# DX_HRII2.net
KiCad netlist of a schematic drawn in EAGLE
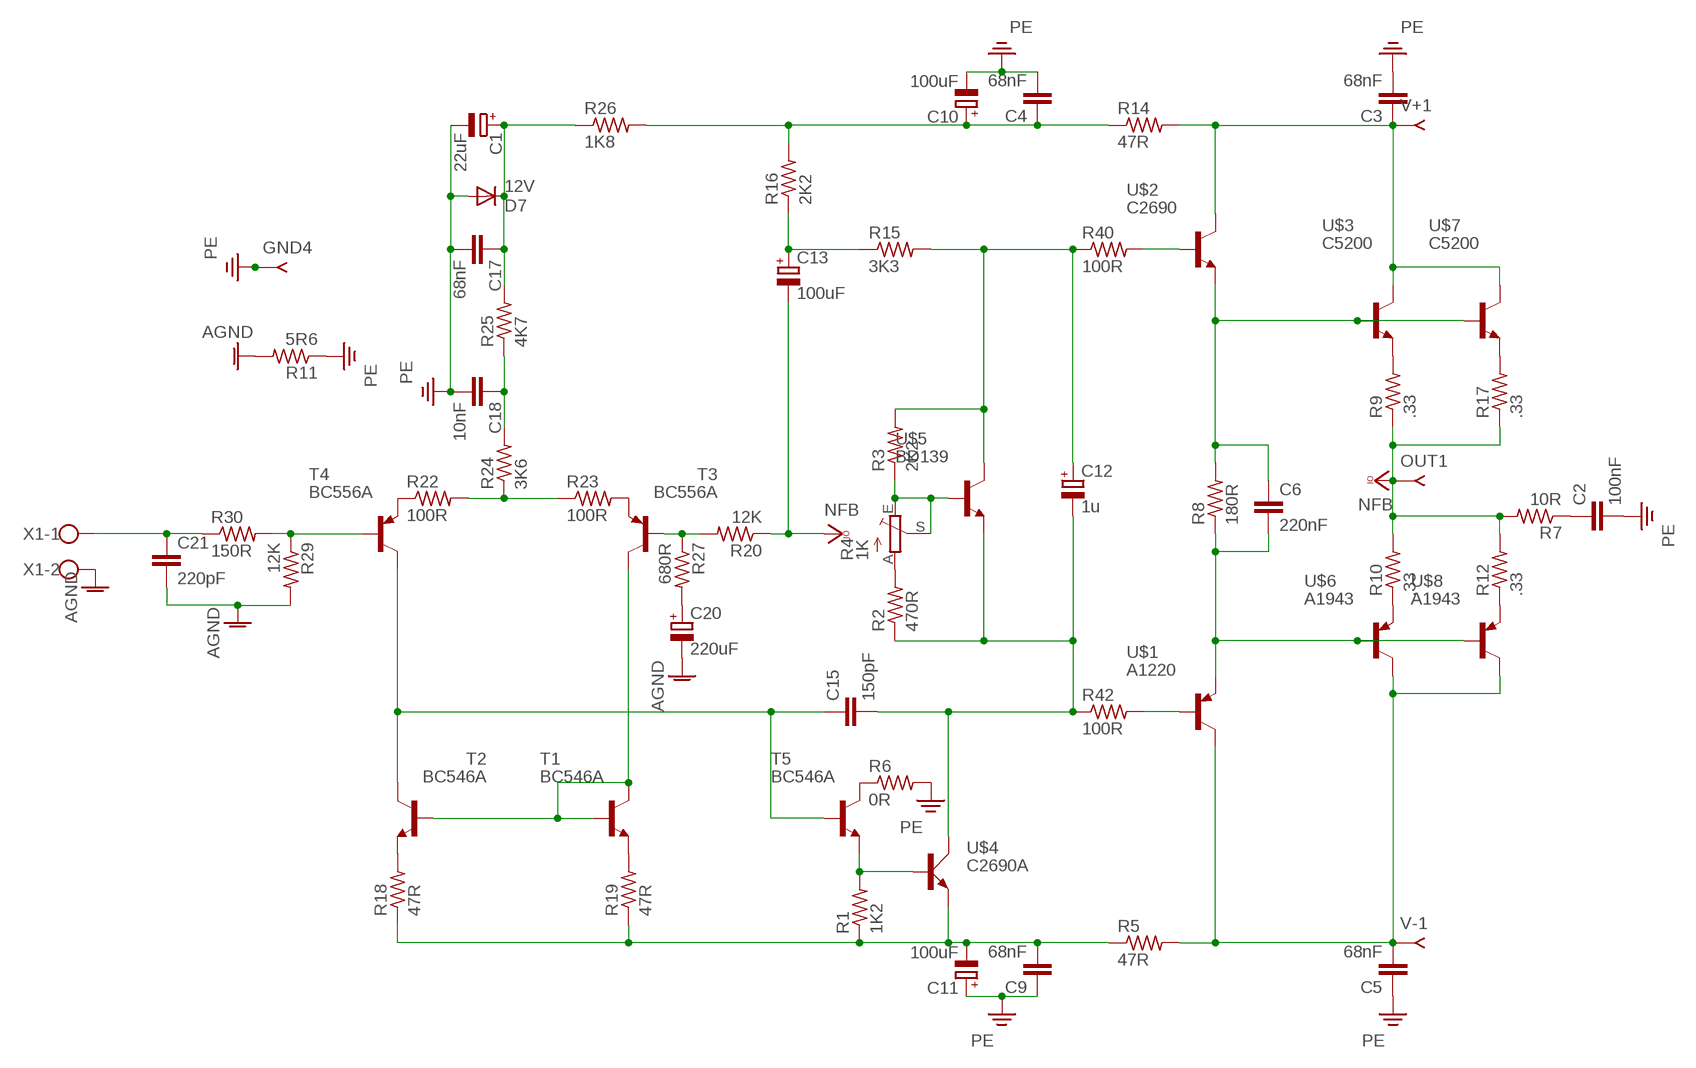
[diagram p0: schematic, sheet 1]

(export (version "E")
  (design (tool "Eeschema 10.0.6"))
  (components
    (comp (ref "C1")
      (value "22uF")
      (footprint "eagle-import:E2,5-6")
      (libsource (lib "eagle-import") (part "CPOL-EUE2.5-6"))
    )
    (comp (ref "C2")
      (value "100nF")
      (footprint "eagle-import:C102-043X133")
      (libsource (lib "eagle-import") (part "C-EU102-043X133"))
    )
    (comp (ref "C3")
      (value "68nF")
      (footprint "eagle-import:C102-043X133")
      (libsource (lib "eagle-import") (part "C-EU102-043X133"))
    )
    (comp (ref "C4")
      (value "68nF")
      (footprint "eagle-import:C050-045X075")
      (libsource (lib "eagle-import") (part "C-EU050-045X075"))
    )
    (comp (ref "C5")
      (value "68nF")
      (footprint "eagle-import:C102-043X133")
      (libsource (lib "eagle-import") (part "C-EU102-043X133"))
    )
    (comp (ref "C6")
      (value "220nF")
      (footprint "eagle-import:C075-052X106")
      (libsource (lib "eagle-import") (part "C-EU075-052X106"))
    )
    (comp (ref "C9")
      (value "68nF")
      (footprint "eagle-import:C050-045X075")
      (libsource (lib "eagle-import") (part "C-EU050-045X075"))
    )
    (comp (ref "C10")
      (value "100uF")
      (footprint "eagle-import:E5-10,5")
      (libsource (lib "eagle-import") (part "CPOL-EUE5-10.5"))
    )
    (comp (ref "C11")
      (value "100uF")
      (footprint "eagle-import:E5-10,5")
      (libsource (lib "eagle-import") (part "CPOL-EUE5-10.5"))
    )
    (comp (ref "C12")
      (value "1u")
      (footprint "eagle-import:E3,5-8")
      (libsource (lib "eagle-import") (part "CPOL-EUE3.5-8"))
    )
    (comp (ref "C13")
      (value "100uF")
      (footprint "eagle-import:E5-13")
      (libsource (lib "eagle-import") (part "CPOL-EUE5-13"))
    )
    (comp (ref "C15")
      (value "150pF")
      (footprint "eagle-import:C050-050X075")
      (libsource (lib "eagle-import") (part "C-EU050-050X075"))
    )
    (comp (ref "C17")
      (value "68nF")
      (footprint "eagle-import:C050-035X075")
      (libsource (lib "eagle-import") (part "C-EU050-035X075"))
    )
    (comp (ref "C18")
      (value "10nF")
      (footprint "eagle-import:C050-055X075")
      (libsource (lib "eagle-import") (part "C-EU050-055X075"))
    )
    (comp (ref "C20")
      (value "220uF")
      (footprint "eagle-import:E5-10,5")
      (libsource (lib "eagle-import") (part "CPOL-EUE5-10.5"))
    )
    (comp (ref "C21")
      (value "220pF")
      (footprint "eagle-import:C050-055X075")
      (libsource (lib "eagle-import") (part "C-EU050-055X075"))
    )
    (comp (ref "D7")
      (value "12V")
      (footprint "eagle-import:DO41-10")
      (libsource (lib "eagle-import") (part "1N4004"))
    )
    (comp (ref "GND4")
      (value "GND")
      (footprint "eagle-import:FASTON")
      (libsource (lib "eagle-import") (part "QFIT"))
    )
    (comp (ref "OUT1")
      (value "QFIT")
      (footprint "eagle-import:FASTON")
      (libsource (lib "eagle-import") (part "QFIT"))
    )
    (comp (ref "R1")
      (value "1K2")
      (footprint "eagle-import:0309_12")
      (libsource (lib "eagle-import") (part "R-US_0309/12"))
    )
    (comp (ref "R2")
      (value "470R")
      (footprint "eagle-import:0309_12")
      (libsource (lib "eagle-import") (part "R-US_0309/12"))
    )
    (comp (ref "R3")
      (value "2K2")
      (footprint "eagle-import:0309_10")
      (libsource (lib "eagle-import") (part "R-US_0309/10"))
    )
    (comp (ref "R4")
      (value "1K")
      (footprint "eagle-import:ECP10P")
      (libsource (lib "eagle-import") (part "TRIM_EU-ECP10P"))
    )
    (comp (ref "R5")
      (value "47R")
      (footprint "eagle-import:0309_12")
      (libsource (lib "eagle-import") (part "R-US_0309/12"))
    )
    (comp (ref "R6")
      (value "0R")
      (footprint "eagle-import:0309_12")
      (libsource (lib "eagle-import") (part "R-US_0309/12"))
    )
    (comp (ref "R7")
      (value "10R")
      (footprint "eagle-import:0309_12")
      (libsource (lib "eagle-import") (part "R-US_0309/12"))
    )
    (comp (ref "R8")
      (value "180R")
      (footprint "eagle-import:0309_10")
      (libsource (lib "eagle-import") (part "R-US_0309/10"))
    )
    (comp (ref "R9")
      (value ".33")
      (footprint "eagle-import:0617_22")
      (libsource (lib "eagle-import") (part "R-US_0617/22"))
    )
    (comp (ref "R10")
      (value ".33")
      (footprint "eagle-import:0617_22")
      (libsource (lib "eagle-import") (part "R-US_0617/22"))
    )
    (comp (ref "R11")
      (value "5R6")
      (footprint "eagle-import:0309_10")
      (libsource (lib "eagle-import") (part "R-US_0309/10"))
    )
    (comp (ref "R12")
      (value ".33")
      (footprint "eagle-import:0617_22")
      (libsource (lib "eagle-import") (part "R-US_0617/22"))
    )
    (comp (ref "R14")
      (value "47R")
      (footprint "eagle-import:0309_12")
      (libsource (lib "eagle-import") (part "R-US_0309/12"))
    )
    (comp (ref "R15")
      (value "3K3")
      (footprint "eagle-import:0309_12")
      (libsource (lib "eagle-import") (part "R-US_0309/12"))
    )
    (comp (ref "R16")
      (value "2K2")
      (footprint "eagle-import:0309_12")
      (libsource (lib "eagle-import") (part "R-US_0309/12"))
    )
    (comp (ref "R17")
      (value ".33")
      (footprint "eagle-import:0617_22")
      (libsource (lib "eagle-import") (part "R-US_0617/22"))
    )
    (comp (ref "R18")
      (value "47R")
      (footprint "eagle-import:0309_12")
      (libsource (lib "eagle-import") (part "R-US_0309/12"))
    )
    (comp (ref "R19")
      (value "47R")
      (footprint "eagle-import:0309_12")
      (libsource (lib "eagle-import") (part "R-US_0309/12"))
    )
    (comp (ref "R20")
      (value "12K")
      (footprint "eagle-import:0309_12")
      (libsource (lib "eagle-import") (part "R-US_0309/12"))
    )
    (comp (ref "R22")
      (value "100R")
      (footprint "eagle-import:0309_10")
      (libsource (lib "eagle-import") (part "R-US_0309/10"))
    )
    (comp (ref "R23")
      (value "100R")
      (footprint "eagle-import:0309_10")
      (libsource (lib "eagle-import") (part "R-US_0309/10"))
    )
    (comp (ref "R24")
      (value "3K6")
      (footprint "eagle-import:0309_10")
      (libsource (lib "eagle-import") (part "R-US_0309/10"))
    )
    (comp (ref "R25")
      (value "4K7")
      (footprint "eagle-import:0309_10")
      (libsource (lib "eagle-import") (part "R-US_0309/10"))
    )
    (comp (ref "R26")
      (value "1K8")
      (footprint "eagle-import:0309_12")
      (libsource (lib "eagle-import") (part "R-US_0309/12"))
    )
    (comp (ref "R27")
      (value "680R")
      (footprint "eagle-import:0309_10")
      (libsource (lib "eagle-import") (part "R-US_0309/10"))
    )
    (comp (ref "R29")
      (value "12K")
      (footprint "eagle-import:0309_10")
      (libsource (lib "eagle-import") (part "R-US_0309/10"))
    )
    (comp (ref "R30")
      (value "150R")
      (footprint "eagle-import:0309_12")
      (libsource (lib "eagle-import") (part "R-US_0309/12"))
    )
    (comp (ref "R40")
      (value "100R")
      (footprint "eagle-import:0309_10")
      (libsource (lib "eagle-import") (part "R-US_0309/10"))
    )
    (comp (ref "R42")
      (value "100R")
      (footprint "eagle-import:0309_10")
      (libsource (lib "eagle-import") (part "R-US_0309/10"))
    )
    (comp (ref "T1")
      (value "BC546A")
      (footprint "eagle-import:TO92-CBE")
      (libsource (lib "eagle-import") (part "-NPN-TO92-CBE"))
    )
    (comp (ref "T2")
      (value "BC546A")
      (footprint "eagle-import:TO92-CBE")
      (libsource (lib "eagle-import") (part "-NPN-TO92-CBE"))
    )
    (comp (ref "T3")
      (value "BC556A")
      (footprint "eagle-import:TO92-CBE")
      (libsource (lib "eagle-import") (part "-PNP-TO92-CBE"))
    )
    (comp (ref "T4")
      (value "BC556A")
      (footprint "eagle-import:TO92-CBE")
      (libsource (lib "eagle-import") (part "-PNP-TO92-CBE"))
    )
    (comp (ref "T5")
      (value "BC546A")
      (footprint "eagle-import:TO92-CBE")
      (libsource (lib "eagle-import") (part "-NPN-TO92-CBE"))
    )
    (comp (ref "U$1")
      (value "A1220")
      (footprint "eagle-import:TO220")
      (libsource (lib "eagle-import") (part "2N6107"))
    )
    (comp (ref "U$2")
      (value "C2690")
      (footprint "eagle-import:TO220")
      (libsource (lib "eagle-import") (part "2N5496"))
    )
    (comp (ref "U$3")
      (value "C5200")
      (footprint "eagle-import:TO-264")
      (libsource (lib "eagle-import") (part "MJL4281"))
    )
    (comp (ref "U$4")
      (value "C2690A")
      (footprint "eagle-import:TO220AV")
      (libsource (lib "eagle-import") (part "TIP41C"))
    )
    (comp (ref "U$5")
      (value "BD139")
      (footprint "eagle-import:TO126")
      (libsource (lib "eagle-import") (part "2N4923"))
    )
    (comp (ref "U$6")
      (value "A1943")
      (footprint "eagle-import:TO-264")
      (libsource (lib "eagle-import") (part "MJL4302"))
    )
    (comp (ref "U$7")
      (value "C5200")
      (footprint "eagle-import:TO-264")
      (libsource (lib "eagle-import") (part "MJL4281"))
    )
    (comp (ref "U$8")
      (value "A1943")
      (footprint "eagle-import:TO-264")
      (libsource (lib "eagle-import") (part "MJL4302"))
    )
    (comp (ref "V+1")
      (value "QFIT")
      (footprint "eagle-import:FASTON")
      (libsource (lib "eagle-import") (part "QFIT"))
    )
    (comp (ref "V-1")
      (value "QFIT")
      (footprint "eagle-import:FASTON")
      (libsource (lib "eagle-import") (part "QFIT"))
    )
    (comp (ref "X1")
      (value "W237-02P")
      (footprint "eagle-import:W237-132")
      (libsource (lib "eagle-import") (part "W237-02P"))
    )
  )
  (nets
    (net (code "1") (name "AGND") (class "Default")
      (node (ref "C20") (pin "-") (pinfunction "-_-") (pintype "passive"))
      (node (ref "C21") (pin "2") (pinfunction "2_2") (pintype "passive"))
      (node (ref "R11") (pin "2") (pinfunction "2_2") (pintype "passive"))
      (node (ref "R29") (pin "2") (pinfunction "2_2") (pintype "passive"))
      (node (ref "X1") (pin "2") (pinfunction "KL_2") (pintype "passive"))
    )
    (net (code "2") (name "NFB") (class "Default")
      (node (ref "C13") (pin "-") (pinfunction "-_-") (pintype "passive"))
      (node (ref "OUT1") (pin "1") (pinfunction "1_1") (pintype "passive"))
      (node (ref "OUT1") (pin "2") (pinfunction "2_2") (pintype "passive"))
      (node (ref "R10") (pin "2") (pinfunction "2_2") (pintype "passive"))
      (node (ref "R12") (pin "2") (pinfunction "2_2") (pintype "passive"))
      (node (ref "R17") (pin "1") (pinfunction "1_1") (pintype "passive"))
      (node (ref "R20") (pin "1") (pinfunction "1_1") (pintype "passive"))
      (node (ref "R7") (pin "2") (pinfunction "2_2") (pintype "passive"))
      (node (ref "R9") (pin "1") (pinfunction "1_1") (pintype "passive"))
    )
    (net (code "3") (name "Net-(C1-Pad+)") (class "Default")
      (node (ref "C1") (pin "+") (pinfunction "+_+") (pintype "passive"))
      (node (ref "C17") (pin "1") (pinfunction "1_1") (pintype "passive"))
      (node (ref "D7") (pin "C") (pinfunction "C_C") (pintype "passive"))
      (node (ref "R25") (pin "2") (pinfunction "2_2") (pintype "passive"))
      (node (ref "R26") (pin "1") (pinfunction "1_1") (pintype "passive"))
    )
    (net (code "4") (name "Net-(C2-Pad1)") (class "Default")
      (node (ref "C2") (pin "1") (pinfunction "1_1") (pintype "passive"))
      (node (ref "R7") (pin "1") (pinfunction "1_1") (pintype "passive"))
    )
    (net (code "5") (name "Net-(C10-Pad+)") (class "Default")
      (node (ref "C10") (pin "+") (pinfunction "+_+") (pintype "passive"))
      (node (ref "C4") (pin "1") (pinfunction "1_1") (pintype "passive"))
      (node (ref "R14") (pin "1") (pinfunction "1_1") (pintype "passive"))
      (node (ref "R16") (pin "2") (pinfunction "2_2") (pintype "passive"))
      (node (ref "R26") (pin "2") (pinfunction "2_2") (pintype "passive"))
    )
    (net (code "6") (name "Net-(C11-Pad-)") (class "Default")
      (node (ref "C11") (pin "-") (pinfunction "-_-") (pintype "passive"))
      (node (ref "C9") (pin "2") (pinfunction "2_2") (pintype "passive"))
      (node (ref "R1") (pin "1") (pinfunction "1_1") (pintype "passive"))
      (node (ref "R18") (pin "1") (pinfunction "1_1") (pintype "passive"))
      (node (ref "R19") (pin "1") (pinfunction "1_1") (pintype "passive"))
      (node (ref "R5") (pin "1") (pinfunction "1_1") (pintype "passive"))
      (node (ref "U$4") (pin "E") (pinfunction "E_E") (pintype "passive"))
    )
    (net (code "7") (name "Net-(C13-Pad+)") (class "Default")
      (node (ref "C13") (pin "+") (pinfunction "+_+") (pintype "passive"))
      (node (ref "R15") (pin "1") (pinfunction "1_1") (pintype "passive"))
      (node (ref "R16") (pin "1") (pinfunction "1_1") (pintype "passive"))
    )
    (net (code "8") (name "Net-(C15-Pad1)") (class "Default")
      (node (ref "C15") (pin "1") (pinfunction "1_1") (pintype "passive"))
      (node (ref "T2") (pin "C") (pinfunction "C_C") (pintype "passive"))
      (node (ref "T4") (pin "C") (pinfunction "C_C") (pintype "passive"))
      (node (ref "T5") (pin "B") (pinfunction "B_B") (pintype "passive"))
    )
    (net (code "9") (name "Net-(C18-Pad1)") (class "Default")
      (node (ref "C18") (pin "1") (pinfunction "1_1") (pintype "passive"))
      (node (ref "R24") (pin "2") (pinfunction "2_2") (pintype "passive"))
      (node (ref "R25") (pin "1") (pinfunction "1_1") (pintype "passive"))
    )
    (net (code "10") (name "Net-(C20-Pad+)") (class "Default")
      (node (ref "C20") (pin "+") (pinfunction "+_+") (pintype "passive"))
      (node (ref "R27") (pin "2") (pinfunction "2_2") (pintype "passive"))
    )
    (net (code "11") (name "Net-(R1-Pad2)") (class "Default")
      (node (ref "R1") (pin "2") (pinfunction "2_2") (pintype "passive"))
      (node (ref "T5") (pin "E") (pinfunction "E_E") (pintype "passive"))
      (node (ref "U$4") (pin "B") (pinfunction "B_B") (pintype "passive"))
    )
    (net (code "12") (name "Net-(R2-Pad2)") (class "Default")
      (node (ref "R2") (pin "2") (pinfunction "2_2") (pintype "passive"))
      (node (ref "R4") (pin "A") (pinfunction "A_A") (pintype "passive"))
    )
    (net (code "13") (name "Net-(R6-Pad1)") (class "Default")
      (node (ref "R6") (pin "1") (pinfunction "1_1") (pintype "passive"))
      (node (ref "T5") (pin "C") (pinfunction "C_C") (pintype "passive"))
    )
    (net (code "14") (name "Net-(R9-Pad2)") (class "Default")
      (node (ref "R9") (pin "2") (pinfunction "2_2") (pintype "passive"))
      (node (ref "U$3") (pin "E") (pinfunction "E_E") (pintype "passive"))
    )
    (net (code "15") (name "Net-(R10-Pad1)") (class "Default")
      (node (ref "R10") (pin "1") (pinfunction "1_1") (pintype "passive"))
      (node (ref "U$6") (pin "E") (pinfunction "E_E") (pintype "passive"))
    )
    (net (code "16") (name "Net-(R12-Pad1)") (class "Default")
      (node (ref "R12") (pin "1") (pinfunction "1_1") (pintype "passive"))
      (node (ref "U$8") (pin "E") (pinfunction "E_E") (pintype "passive"))
    )
    (net (code "17") (name "Net-(R17-Pad2)") (class "Default")
      (node (ref "R17") (pin "2") (pinfunction "2_2") (pintype "passive"))
      (node (ref "U$7") (pin "E") (pinfunction "E_E") (pintype "passive"))
    )
    (net (code "18") (name "Net-(R18-Pad2)") (class "Default")
      (node (ref "R18") (pin "2") (pinfunction "2_2") (pintype "passive"))
      (node (ref "T2") (pin "E") (pinfunction "E_E") (pintype "passive"))
    )
    (net (code "19") (name "Net-(R19-Pad2)") (class "Default")
      (node (ref "R19") (pin "2") (pinfunction "2_2") (pintype "passive"))
      (node (ref "T1") (pin "E") (pinfunction "E_E") (pintype "passive"))
    )
    (net (code "20") (name "Net-(R20-Pad2)") (class "Default")
      (node (ref "R20") (pin "2") (pinfunction "2_2") (pintype "passive"))
      (node (ref "R27") (pin "1") (pinfunction "1_1") (pintype "passive"))
      (node (ref "T3") (pin "B") (pinfunction "B_B") (pintype "passive"))
    )
    (net (code "21") (name "Net-(R22-Pad1)") (class "Default")
      (node (ref "R22") (pin "1") (pinfunction "1_1") (pintype "passive"))
      (node (ref "T4") (pin "E") (pinfunction "E_E") (pintype "passive"))
    )
    (net (code "22") (name "Net-(R22-Pad2)") (class "Default")
      (node (ref "R22") (pin "2") (pinfunction "2_2") (pintype "passive"))
      (node (ref "R23") (pin "1") (pinfunction "1_1") (pintype "passive"))
      (node (ref "R24") (pin "1") (pinfunction "1_1") (pintype "passive"))
    )
    (net (code "23") (name "Net-(R23-Pad2)") (class "Default")
      (node (ref "R23") (pin "2") (pinfunction "2_2") (pintype "passive"))
      (node (ref "T3") (pin "E") (pinfunction "E_E") (pintype "passive"))
    )
    (net (code "24") (name "Net-(R29-Pad1)") (class "Default")
      (node (ref "R29") (pin "1") (pinfunction "1_1") (pintype "passive"))
      (node (ref "R30") (pin "2") (pinfunction "2_2") (pintype "passive"))
      (node (ref "T4") (pin "B") (pinfunction "B_B") (pintype "passive"))
    )
    (net (code "25") (name "Net-(T1-PadB)") (class "Default")
      (node (ref "T1") (pin "B") (pinfunction "B_B") (pintype "passive"))
      (node (ref "T1") (pin "C") (pinfunction "C_C") (pintype "passive"))
      (node (ref "T2") (pin "B") (pinfunction "B_B") (pintype "passive"))
      (node (ref "T3") (pin "C") (pinfunction "C_C") (pintype "passive"))
    )
    (net (code "26") (name "Net-(U$1-B)") (class "Default")
      (node (ref "R42") (pin "2") (pinfunction "2_2") (pintype "passive"))
      (node (ref "U$1") (pin "1") (pinfunction "B_1") (pintype "passive"))
    )
    (net (code "27") (name "Net-(U$1-C)") (class "Default")
      (node (ref "C5") (pin "2") (pinfunction "2_2") (pintype "passive"))
      (node (ref "R5") (pin "2") (pinfunction "2_2") (pintype "passive"))
      (node (ref "U$1") (pin "2") (pinfunction "C_2") (pintype "passive"))
      (node (ref "U$6") (pin "C") (pinfunction "C_C") (pintype "passive"))
      (node (ref "U$8") (pin "C") (pinfunction "C_C") (pintype "passive"))
      (node (ref "V-1") (pin "1") (pinfunction "1_1") (pintype "passive"))
      (node (ref "V-1") (pin "2") (pinfunction "2_2") (pintype "passive"))
    )
    (net (code "28") (name "Net-(U$1-E)") (class "Default")
      (node (ref "C6") (pin "2") (pinfunction "2_2") (pintype "passive"))
      (node (ref "R8") (pin "1") (pinfunction "1_1") (pintype "passive"))
      (node (ref "U$1") (pin "3") (pinfunction "E_3") (pintype "passive"))
      (node (ref "U$6") (pin "B") (pinfunction "B_B") (pintype "passive"))
      (node (ref "U$8") (pin "B") (pinfunction "B_B") (pintype "passive"))
    )
    (net (code "29") (name "Net-(U$2-B)") (class "Default")
      (node (ref "R40") (pin "2") (pinfunction "2_2") (pintype "passive"))
      (node (ref "U$2") (pin "1") (pinfunction "B_1") (pintype "passive"))
    )
    (net (code "30") (name "Net-(U$2-C)") (class "Default")
      (node (ref "C3") (pin "1") (pinfunction "1_1") (pintype "passive"))
      (node (ref "R14") (pin "2") (pinfunction "2_2") (pintype "passive"))
      (node (ref "U$2") (pin "2") (pinfunction "C_2") (pintype "passive"))
      (node (ref "U$3") (pin "C") (pinfunction "C_C") (pintype "passive"))
      (node (ref "U$7") (pin "C") (pinfunction "C_C") (pintype "passive"))
      (node (ref "V+1") (pin "1") (pinfunction "1_1") (pintype "passive"))
      (node (ref "V+1") (pin "2") (pinfunction "2_2") (pintype "passive"))
    )
    (net (code "31") (name "Net-(U$2-E)") (class "Default")
      (node (ref "C6") (pin "1") (pinfunction "1_1") (pintype "passive"))
      (node (ref "R8") (pin "2") (pinfunction "2_2") (pintype "passive"))
      (node (ref "U$2") (pin "3") (pinfunction "E_3") (pintype "passive"))
      (node (ref "U$3") (pin "B") (pinfunction "B_B") (pintype "passive"))
      (node (ref "U$7") (pin "B") (pinfunction "B_B") (pintype "passive"))
    )
    (net (code "32") (name "Net-(U$5-B)") (class "Default")
      (node (ref "R3") (pin "1") (pinfunction "1_1") (pintype "passive"))
      (node (ref "R4") (pin "E") (pinfunction "E_E") (pintype "passive"))
      (node (ref "R4") (pin "S") (pinfunction "S_S") (pintype "passive"))
      (node (ref "U$5") (pin "3") (pinfunction "B_3") (pintype "passive"))
    )
    (net (code "33") (name "Net-(U$5-C)") (class "Default")
      (node (ref "C12") (pin "+") (pinfunction "+_+") (pintype "passive"))
      (node (ref "R15") (pin "2") (pinfunction "2_2") (pintype "passive"))
      (node (ref "R3") (pin "2") (pinfunction "2_2") (pintype "passive"))
      (node (ref "R40") (pin "1") (pinfunction "1_1") (pintype "passive"))
      (node (ref "U$5") (pin "2") (pinfunction "C_2") (pintype "passive"))
    )
    (net (code "34") (name "Net-(U$5-E)") (class "Default")
      (node (ref "C12") (pin "-") (pinfunction "-_-") (pintype "passive"))
      (node (ref "C15") (pin "2") (pinfunction "2_2") (pintype "passive"))
      (node (ref "R2") (pin "1") (pinfunction "1_1") (pintype "passive"))
      (node (ref "R42") (pin "1") (pinfunction "1_1") (pintype "passive"))
      (node (ref "U$4") (pin "C") (pinfunction "C_C") (pintype "passive"))
      (node (ref "U$5") (pin "1") (pinfunction "E_1") (pintype "passive"))
    )
    (net (code "35") (name "Net-(X1A-KL)") (class "Default")
      (node (ref "C21") (pin "1") (pinfunction "1_1") (pintype "passive"))
      (node (ref "R30") (pin "1") (pinfunction "1_1") (pintype "passive"))
      (node (ref "X1") (pin "1") (pinfunction "KL_1") (pintype "passive"))
    )
    (net (code "36") (name "PE") (class "Default")
      (node (ref "C1") (pin "-") (pinfunction "-_-") (pintype "passive"))
      (node (ref "C10") (pin "-") (pinfunction "-_-") (pintype "passive"))
      (node (ref "C11") (pin "+") (pinfunction "+_+") (pintype "passive"))
      (node (ref "C17") (pin "2") (pinfunction "2_2") (pintype "passive"))
      (node (ref "C18") (pin "2") (pinfunction "2_2") (pintype "passive"))
      (node (ref "C2") (pin "2") (pinfunction "2_2") (pintype "passive"))
      (node (ref "C3") (pin "2") (pinfunction "2_2") (pintype "passive"))
      (node (ref "C4") (pin "2") (pinfunction "2_2") (pintype "passive"))
      (node (ref "C5") (pin "1") (pinfunction "1_1") (pintype "passive"))
      (node (ref "C9") (pin "1") (pinfunction "1_1") (pintype "passive"))
      (node (ref "D7") (pin "A") (pinfunction "A_A") (pintype "passive"))
      (node (ref "GND4") (pin "1") (pinfunction "1_1") (pintype "passive"))
      (node (ref "GND4") (pin "2") (pinfunction "2_2") (pintype "passive"))
      (node (ref "R11") (pin "1") (pinfunction "1_1") (pintype "passive"))
      (node (ref "R6") (pin "2") (pinfunction "2_2") (pintype "passive"))
    )
  )
)
